# Gyro_MPU9250.net
KiCad netlist of a schematic drawn in EAGLE
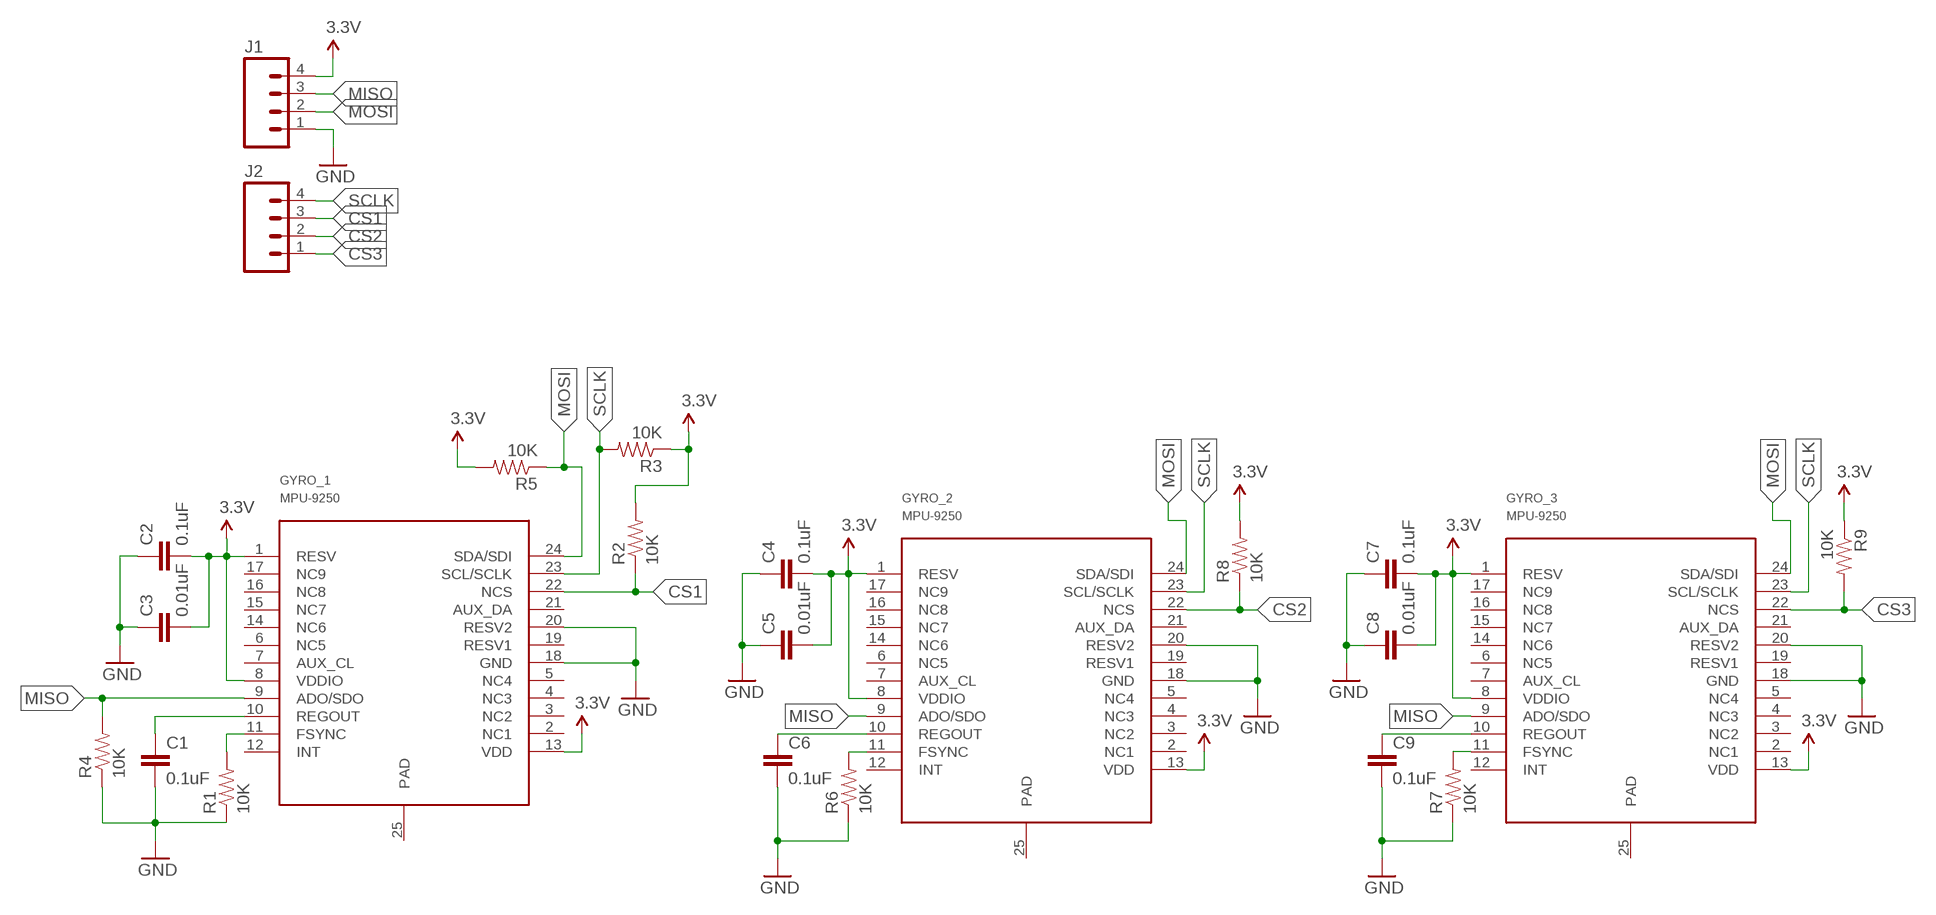
[diagram p0: schematic, sheet 1]

(export (version "E")
  (design (tool "Eeschema 10.0.6"))
  (components
    (comp (ref "C1")
      (value "0.1uF")
      (footprint "eagle-import:0603-CAP")
      (libsource (lib "eagle-import") (part "CAP0603-CAP"))
    )
    (comp (ref "C2")
      (value "0.1uF")
      (footprint "eagle-import:0603-CAP")
      (libsource (lib "eagle-import") (part "CAP0603-CAP"))
    )
    (comp (ref "C3")
      (value "0.01uF")
      (footprint "eagle-import:0603-CAP")
      (libsource (lib "eagle-import") (part "CAP0603-CAP"))
    )
    (comp (ref "C4")
      (value "0.1uF")
      (footprint "eagle-import:0603-CAP")
      (libsource (lib "eagle-import") (part "CAP0603-CAP"))
    )
    (comp (ref "C5")
      (value "0.01uF")
      (footprint "eagle-import:0603-CAP")
      (libsource (lib "eagle-import") (part "CAP0603-CAP"))
    )
    (comp (ref "C6")
      (value "0.1uF")
      (footprint "eagle-import:0603-CAP")
      (libsource (lib "eagle-import") (part "CAP0603-CAP"))
    )
    (comp (ref "C7")
      (value "0.1uF")
      (footprint "eagle-import:0603-CAP")
      (libsource (lib "eagle-import") (part "CAP0603-CAP"))
    )
    (comp (ref "C8")
      (value "0.01uF")
      (footprint "eagle-import:0603-CAP")
      (libsource (lib "eagle-import") (part "CAP0603-CAP"))
    )
    (comp (ref "C9")
      (value "0.1uF")
      (footprint "eagle-import:0603-CAP")
      (libsource (lib "eagle-import") (part "CAP0603-CAP"))
    )
    (comp (ref "GYRO_1")
      (value "MPU-9250")
      (footprint "eagle-import:LEAD-QFN24")
      (libsource (lib "eagle-import") (part "MPU-9250"))
    )
    (comp (ref "GYRO_2")
      (value "MPU-9250")
      (footprint "eagle-import:LEAD-QFN24")
      (libsource (lib "eagle-import") (part "MPU-9250"))
    )
    (comp (ref "GYRO_3")
      (value "MPU-9250")
      (footprint "eagle-import:LEAD-QFN24")
      (libsource (lib "eagle-import") (part "MPU-9250"))
    )
    (comp (ref "J1")
      (value "M04PTH")
      (footprint "eagle-import:1X04")
      (libsource (lib "eagle-import") (part "M04PTH"))
    )
    (comp (ref "J2")
      (value "M04PTH")
      (footprint "eagle-import:1X04")
      (libsource (lib "eagle-import") (part "M04PTH"))
    )
    (comp (ref "R1")
      (value "10K")
      (footprint "eagle-import:0603-RES")
      (libsource (lib "eagle-import") (part "RESISTOR0603-RES"))
    )
    (comp (ref "R2")
      (value "10K")
      (footprint "eagle-import:0603-RES")
      (libsource (lib "eagle-import") (part "RESISTOR0603-RES"))
    )
    (comp (ref "R3")
      (value "10K")
      (footprint "eagle-import:0603-RES")
      (libsource (lib "eagle-import") (part "RESISTOR0603-RES"))
    )
    (comp (ref "R4")
      (value "10K")
      (footprint "eagle-import:0603-RES")
      (libsource (lib "eagle-import") (part "RESISTOR0603-RES"))
    )
    (comp (ref "R5")
      (value "10K")
      (footprint "eagle-import:0603-RES")
      (libsource (lib "eagle-import") (part "RESISTOR0603-RES"))
    )
    (comp (ref "R6")
      (value "10K")
      (footprint "eagle-import:0603-RES")
      (libsource (lib "eagle-import") (part "RESISTOR0603-RES"))
    )
    (comp (ref "R7")
      (value "10K")
      (footprint "eagle-import:0603-RES")
      (libsource (lib "eagle-import") (part "RESISTOR0603-RES"))
    )
    (comp (ref "R8")
      (value "10K")
      (footprint "eagle-import:0603-RES")
      (libsource (lib "eagle-import") (part "RESISTOR0603-RES"))
    )
    (comp (ref "R9")
      (value "10K")
      (footprint "eagle-import:0603-RES")
      (libsource (lib "eagle-import") (part "RESISTOR0603-RES"))
    )
  )
  (nets
    (net (code "1") (name "3.3V") (class "Default")
      (node (ref "C2") (pin "2") (pinfunction "2_2") (pintype "passive"))
      (node (ref "C3") (pin "2") (pinfunction "2_2") (pintype "passive"))
      (node (ref "C4") (pin "2") (pinfunction "2_2") (pintype "passive"))
      (node (ref "C5") (pin "2") (pinfunction "2_2") (pintype "passive"))
      (node (ref "C7") (pin "2") (pinfunction "2_2") (pintype "passive"))
      (node (ref "C8") (pin "2") (pinfunction "2_2") (pintype "passive"))
      (node (ref "GYRO_1") (pin "1") (pinfunction "RESV_1") (pintype "bidirectional"))
      (node (ref "GYRO_1") (pin "13") (pinfunction "VDD_13") (pintype "bidirectional"))
      (node (ref "GYRO_1") (pin "8") (pinfunction "VDDIO_8") (pintype "bidirectional"))
      (node (ref "GYRO_2") (pin "1") (pinfunction "RESV_1") (pintype "bidirectional"))
      (node (ref "GYRO_2") (pin "13") (pinfunction "VDD_13") (pintype "bidirectional"))
      (node (ref "GYRO_2") (pin "8") (pinfunction "VDDIO_8") (pintype "bidirectional"))
      (node (ref "GYRO_3") (pin "1") (pinfunction "RESV_1") (pintype "bidirectional"))
      (node (ref "GYRO_3") (pin "13") (pinfunction "VDD_13") (pintype "bidirectional"))
      (node (ref "GYRO_3") (pin "8") (pinfunction "VDDIO_8") (pintype "bidirectional"))
      (node (ref "J1") (pin "4") (pinfunction "4_4") (pintype "passive"))
      (node (ref "R2") (pin "2") (pinfunction "2_2") (pintype "passive"))
      (node (ref "R3") (pin "1") (pinfunction "1_1") (pintype "passive"))
      (node (ref "R5") (pin "2") (pinfunction "2_2") (pintype "passive"))
      (node (ref "R8") (pin "2") (pinfunction "2_2") (pintype "passive"))
      (node (ref "R9") (pin "1") (pinfunction "1_1") (pintype "passive"))
    )
    (net (code "2") (name "CS1") (class "Default")
      (node (ref "GYRO_1") (pin "22") (pinfunction "NCS_22") (pintype "bidirectional"))
      (node (ref "J2") (pin "3") (pinfunction "3_3") (pintype "passive"))
      (node (ref "R2") (pin "1") (pinfunction "1_1") (pintype "passive"))
    )
    (net (code "3") (name "CS2") (class "Default")
      (node (ref "GYRO_2") (pin "22") (pinfunction "NCS_22") (pintype "bidirectional"))
      (node (ref "J2") (pin "2") (pinfunction "2_2") (pintype "passive"))
      (node (ref "R8") (pin "1") (pinfunction "1_1") (pintype "passive"))
    )
    (net (code "4") (name "CS3") (class "Default")
      (node (ref "GYRO_3") (pin "22") (pinfunction "NCS_22") (pintype "bidirectional"))
      (node (ref "J2") (pin "1") (pinfunction "1_1") (pintype "passive"))
      (node (ref "R9") (pin "2") (pinfunction "2_2") (pintype "passive"))
    )
    (net (code "5") (name "GND") (class "Default")
      (node (ref "C1") (pin "2") (pinfunction "2_2") (pintype "passive"))
      (node (ref "C2") (pin "1") (pinfunction "1_1") (pintype "passive"))
      (node (ref "C3") (pin "1") (pinfunction "1_1") (pintype "passive"))
      (node (ref "C4") (pin "1") (pinfunction "1_1") (pintype "passive"))
      (node (ref "C5") (pin "1") (pinfunction "1_1") (pintype "passive"))
      (node (ref "C6") (pin "2") (pinfunction "2_2") (pintype "passive"))
      (node (ref "C7") (pin "1") (pinfunction "1_1") (pintype "passive"))
      (node (ref "C8") (pin "1") (pinfunction "1_1") (pintype "passive"))
      (node (ref "C9") (pin "2") (pinfunction "2_2") (pintype "passive"))
      (node (ref "GYRO_1") (pin "18") (pinfunction "GND_18") (pintype "bidirectional"))
      (node (ref "GYRO_1") (pin "20") (pinfunction "RESV2_20") (pintype "bidirectional"))
      (node (ref "GYRO_2") (pin "18") (pinfunction "GND_18") (pintype "bidirectional"))
      (node (ref "GYRO_2") (pin "20") (pinfunction "RESV2_20") (pintype "bidirectional"))
      (node (ref "GYRO_3") (pin "18") (pinfunction "GND_18") (pintype "bidirectional"))
      (node (ref "GYRO_3") (pin "20") (pinfunction "RESV2_20") (pintype "bidirectional"))
      (node (ref "J1") (pin "1") (pinfunction "1_1") (pintype "passive"))
      (node (ref "R1") (pin "1") (pinfunction "1_1") (pintype "passive"))
      (node (ref "R4") (pin "1") (pinfunction "1_1") (pintype "passive"))
      (node (ref "R6") (pin "1") (pinfunction "1_1") (pintype "passive"))
      (node (ref "R7") (pin "1") (pinfunction "1_1") (pintype "passive"))
    )
    (net (code "6") (name "MISO") (class "Default")
      (node (ref "GYRO_1") (pin "9") (pinfunction "ADO/SDO_9") (pintype "bidirectional"))
      (node (ref "GYRO_2") (pin "9") (pinfunction "ADO/SDO_9") (pintype "bidirectional"))
      (node (ref "GYRO_3") (pin "9") (pinfunction "ADO/SDO_9") (pintype "bidirectional"))
      (node (ref "J1") (pin "3") (pinfunction "3_3") (pintype "passive"))
      (node (ref "R4") (pin "2") (pinfunction "2_2") (pintype "passive"))
    )
    (net (code "7") (name "MOSI") (class "Default")
      (node (ref "GYRO_1") (pin "24") (pinfunction "SDA/SDI_24") (pintype "bidirectional"))
      (node (ref "GYRO_2") (pin "24") (pinfunction "SDA/SDI_24") (pintype "bidirectional"))
      (node (ref "GYRO_3") (pin "24") (pinfunction "SDA/SDI_24") (pintype "bidirectional"))
      (node (ref "J1") (pin "2") (pinfunction "2_2") (pintype "passive"))
      (node (ref "R5") (pin "1") (pinfunction "1_1") (pintype "passive"))
    )
    (net (code "8") (name "Net-(GYRO_1-FSYNC)") (class "Default")
      (node (ref "GYRO_1") (pin "11") (pinfunction "FSYNC_11") (pintype "bidirectional"))
      (node (ref "R1") (pin "2") (pinfunction "2_2") (pintype "passive"))
    )
    (net (code "9") (name "Net-(GYRO_1-REGOUT)") (class "Default")
      (node (ref "C1") (pin "1") (pinfunction "1_1") (pintype "passive"))
      (node (ref "GYRO_1") (pin "10") (pinfunction "REGOUT_10") (pintype "bidirectional"))
    )
    (net (code "10") (name "Net-(GYRO_2-FSYNC)") (class "Default")
      (node (ref "GYRO_2") (pin "11") (pinfunction "FSYNC_11") (pintype "bidirectional"))
      (node (ref "R6") (pin "2") (pinfunction "2_2") (pintype "passive"))
    )
    (net (code "11") (name "Net-(GYRO_2-REGOUT)") (class "Default")
      (node (ref "C6") (pin "1") (pinfunction "1_1") (pintype "passive"))
      (node (ref "GYRO_2") (pin "10") (pinfunction "REGOUT_10") (pintype "bidirectional"))
    )
    (net (code "12") (name "Net-(GYRO_3-FSYNC)") (class "Default")
      (node (ref "GYRO_3") (pin "11") (pinfunction "FSYNC_11") (pintype "bidirectional"))
      (node (ref "R7") (pin "2") (pinfunction "2_2") (pintype "passive"))
    )
    (net (code "13") (name "Net-(GYRO_3-REGOUT)") (class "Default")
      (node (ref "C9") (pin "1") (pinfunction "1_1") (pintype "passive"))
      (node (ref "GYRO_3") (pin "10") (pinfunction "REGOUT_10") (pintype "bidirectional"))
    )
    (net (code "14") (name "SCLK") (class "Default")
      (node (ref "GYRO_1") (pin "23") (pinfunction "SCL/SCLK_23") (pintype "bidirectional"))
      (node (ref "GYRO_2") (pin "23") (pinfunction "SCL/SCLK_23") (pintype "bidirectional"))
      (node (ref "GYRO_3") (pin "23") (pinfunction "SCL/SCLK_23") (pintype "bidirectional"))
      (node (ref "J2") (pin "4") (pinfunction "4_4") (pintype "passive"))
      (node (ref "R3") (pin "2") (pinfunction "2_2") (pintype "passive"))
    )
    (net (code "15") (name "unconnected-(GYRO_1-AUX_CL-Pad7)") (class "Default")
      (node (ref "GYRO_1") (pin "7") (pinfunction "AUX_CL_7") (pintype "bidirectional"))
    )
    (net (code "16") (name "unconnected-(GYRO_1-AUX_DA-Pad21)") (class "Default")
      (node (ref "GYRO_1") (pin "21") (pinfunction "AUX_DA_21") (pintype "bidirectional"))
    )
    (net (code "17") (name "unconnected-(GYRO_1-INT-Pad12)") (class "Default")
      (node (ref "GYRO_1") (pin "12") (pinfunction "INT_12") (pintype "bidirectional"))
    )
    (net (code "18") (name "unconnected-(GYRO_1-NC1-Pad2)") (class "Default")
      (node (ref "GYRO_1") (pin "2") (pinfunction "NC1_2") (pintype "bidirectional"))
    )
    (net (code "19") (name "unconnected-(GYRO_1-NC2-Pad3)") (class "Default")
      (node (ref "GYRO_1") (pin "3") (pinfunction "NC2_3") (pintype "bidirectional"))
    )
    (net (code "20") (name "unconnected-(GYRO_1-NC3-Pad4)") (class "Default")
      (node (ref "GYRO_1") (pin "4") (pinfunction "NC3_4") (pintype "bidirectional"))
    )
    (net (code "21") (name "unconnected-(GYRO_1-NC4-Pad5)") (class "Default")
      (node (ref "GYRO_1") (pin "5") (pinfunction "NC4_5") (pintype "bidirectional"))
    )
    (net (code "22") (name "unconnected-(GYRO_1-NC5-Pad6)") (class "Default")
      (node (ref "GYRO_1") (pin "6") (pinfunction "NC5_6") (pintype "bidirectional"))
    )
    (net (code "23") (name "unconnected-(GYRO_1-NC6-Pad14)") (class "Default")
      (node (ref "GYRO_1") (pin "14") (pinfunction "NC6_14") (pintype "bidirectional"))
    )
    (net (code "24") (name "unconnected-(GYRO_1-NC7-Pad15)") (class "Default")
      (node (ref "GYRO_1") (pin "15") (pinfunction "NC7_15") (pintype "bidirectional"))
    )
    (net (code "25") (name "unconnected-(GYRO_1-NC8-Pad16)") (class "Default")
      (node (ref "GYRO_1") (pin "16") (pinfunction "NC8_16") (pintype "bidirectional"))
    )
    (net (code "26") (name "unconnected-(GYRO_1-NC9-Pad17)") (class "Default")
      (node (ref "GYRO_1") (pin "17") (pinfunction "NC9_17") (pintype "bidirectional"))
    )
    (net (code "27") (name "unconnected-(GYRO_1-PAD-Pad25)") (class "Default")
      (node (ref "GYRO_1") (pin "25") (pinfunction "PAD_25") (pintype "bidirectional"))
    )
    (net (code "28") (name "unconnected-(GYRO_1-RESV1-Pad19)") (class "Default")
      (node (ref "GYRO_1") (pin "19") (pinfunction "RESV1_19") (pintype "bidirectional"))
    )
    (net (code "29") (name "unconnected-(GYRO_2-AUX_CL-Pad7)") (class "Default")
      (node (ref "GYRO_2") (pin "7") (pinfunction "AUX_CL_7") (pintype "bidirectional"))
    )
    (net (code "30") (name "unconnected-(GYRO_2-AUX_DA-Pad21)") (class "Default")
      (node (ref "GYRO_2") (pin "21") (pinfunction "AUX_DA_21") (pintype "bidirectional"))
    )
    (net (code "31") (name "unconnected-(GYRO_2-INT-Pad12)") (class "Default")
      (node (ref "GYRO_2") (pin "12") (pinfunction "INT_12") (pintype "bidirectional"))
    )
    (net (code "32") (name "unconnected-(GYRO_2-NC1-Pad2)") (class "Default")
      (node (ref "GYRO_2") (pin "2") (pinfunction "NC1_2") (pintype "bidirectional"))
    )
    (net (code "33") (name "unconnected-(GYRO_2-NC2-Pad3)") (class "Default")
      (node (ref "GYRO_2") (pin "3") (pinfunction "NC2_3") (pintype "bidirectional"))
    )
    (net (code "34") (name "unconnected-(GYRO_2-NC3-Pad4)") (class "Default")
      (node (ref "GYRO_2") (pin "4") (pinfunction "NC3_4") (pintype "bidirectional"))
    )
    (net (code "35") (name "unconnected-(GYRO_2-NC4-Pad5)") (class "Default")
      (node (ref "GYRO_2") (pin "5") (pinfunction "NC4_5") (pintype "bidirectional"))
    )
    (net (code "36") (name "unconnected-(GYRO_2-NC5-Pad6)") (class "Default")
      (node (ref "GYRO_2") (pin "6") (pinfunction "NC5_6") (pintype "bidirectional"))
    )
    (net (code "37") (name "unconnected-(GYRO_2-NC6-Pad14)") (class "Default")
      (node (ref "GYRO_2") (pin "14") (pinfunction "NC6_14") (pintype "bidirectional"))
    )
    (net (code "38") (name "unconnected-(GYRO_2-NC7-Pad15)") (class "Default")
      (node (ref "GYRO_2") (pin "15") (pinfunction "NC7_15") (pintype "bidirectional"))
    )
    (net (code "39") (name "unconnected-(GYRO_2-NC8-Pad16)") (class "Default")
      (node (ref "GYRO_2") (pin "16") (pinfunction "NC8_16") (pintype "bidirectional"))
    )
    (net (code "40") (name "unconnected-(GYRO_2-NC9-Pad17)") (class "Default")
      (node (ref "GYRO_2") (pin "17") (pinfunction "NC9_17") (pintype "bidirectional"))
    )
    (net (code "41") (name "unconnected-(GYRO_2-PAD-Pad25)") (class "Default")
      (node (ref "GYRO_2") (pin "25") (pinfunction "PAD_25") (pintype "bidirectional"))
    )
    (net (code "42") (name "unconnected-(GYRO_2-RESV1-Pad19)") (class "Default")
      (node (ref "GYRO_2") (pin "19") (pinfunction "RESV1_19") (pintype "bidirectional"))
    )
    (net (code "43") (name "unconnected-(GYRO_3-AUX_CL-Pad7)") (class "Default")
      (node (ref "GYRO_3") (pin "7") (pinfunction "AUX_CL_7") (pintype "bidirectional"))
    )
    (net (code "44") (name "unconnected-(GYRO_3-AUX_DA-Pad21)") (class "Default")
      (node (ref "GYRO_3") (pin "21") (pinfunction "AUX_DA_21") (pintype "bidirectional"))
    )
    (net (code "45") (name "unconnected-(GYRO_3-INT-Pad12)") (class "Default")
      (node (ref "GYRO_3") (pin "12") (pinfunction "INT_12") (pintype "bidirectional"))
    )
    (net (code "46") (name "unconnected-(GYRO_3-NC1-Pad2)") (class "Default")
      (node (ref "GYRO_3") (pin "2") (pinfunction "NC1_2") (pintype "bidirectional"))
    )
    (net (code "47") (name "unconnected-(GYRO_3-NC2-Pad3)") (class "Default")
      (node (ref "GYRO_3") (pin "3") (pinfunction "NC2_3") (pintype "bidirectional"))
    )
    (net (code "48") (name "unconnected-(GYRO_3-NC3-Pad4)") (class "Default")
      (node (ref "GYRO_3") (pin "4") (pinfunction "NC3_4") (pintype "bidirectional"))
    )
    (net (code "49") (name "unconnected-(GYRO_3-NC4-Pad5)") (class "Default")
      (node (ref "GYRO_3") (pin "5") (pinfunction "NC4_5") (pintype "bidirectional"))
    )
    (net (code "50") (name "unconnected-(GYRO_3-NC5-Pad6)") (class "Default")
      (node (ref "GYRO_3") (pin "6") (pinfunction "NC5_6") (pintype "bidirectional"))
    )
    (net (code "51") (name "unconnected-(GYRO_3-NC6-Pad14)") (class "Default")
      (node (ref "GYRO_3") (pin "14") (pinfunction "NC6_14") (pintype "bidirectional"))
    )
    (net (code "52") (name "unconnected-(GYRO_3-NC7-Pad15)") (class "Default")
      (node (ref "GYRO_3") (pin "15") (pinfunction "NC7_15") (pintype "bidirectional"))
    )
    (net (code "53") (name "unconnected-(GYRO_3-NC8-Pad16)") (class "Default")
      (node (ref "GYRO_3") (pin "16") (pinfunction "NC8_16") (pintype "bidirectional"))
    )
    (net (code "54") (name "unconnected-(GYRO_3-NC9-Pad17)") (class "Default")
      (node (ref "GYRO_3") (pin "17") (pinfunction "NC9_17") (pintype "bidirectional"))
    )
    (net (code "55") (name "unconnected-(GYRO_3-PAD-Pad25)") (class "Default")
      (node (ref "GYRO_3") (pin "25") (pinfunction "PAD_25") (pintype "bidirectional"))
    )
    (net (code "56") (name "unconnected-(GYRO_3-RESV1-Pad19)") (class "Default")
      (node (ref "GYRO_3") (pin "19") (pinfunction "RESV1_19") (pintype "bidirectional"))
    )
  )
)
